# antenna.net
KiCad netlist of a schematic drawn in EAGLE
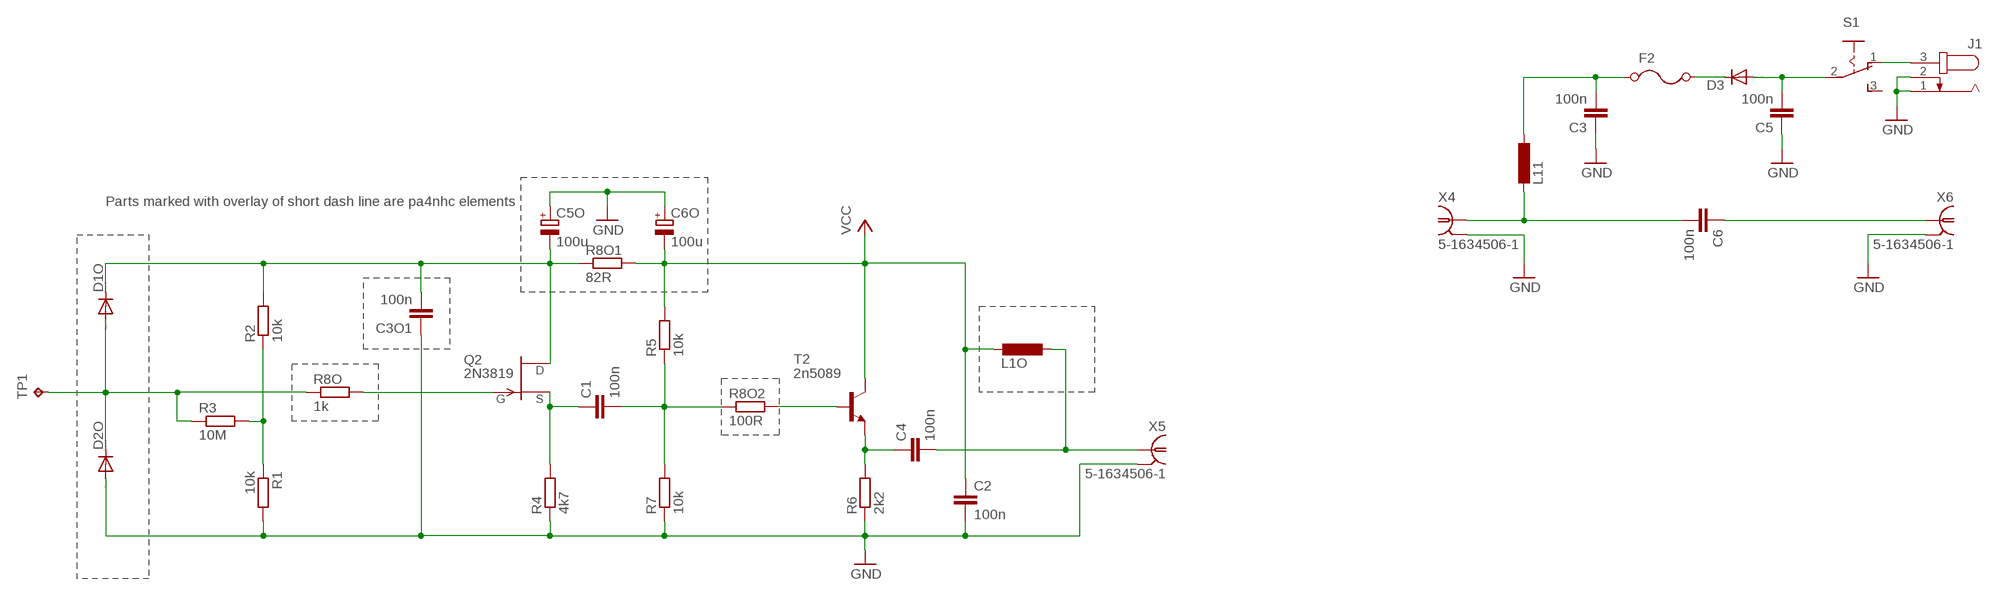
[diagram p0: schematic, sheet 1]

(export (version "E")
  (design (tool "Eeschema 10.0.6"))
  (components
    (comp (ref "C1")
      (value "100n")
      (footprint "eagle-import:C0805")
      (fields (field (name "MFR") "C0805C104K5RACTU"))
      (libsource (lib "eagle-import") (part "C-EUC0805"))
    )
    (comp (ref "C2")
      (value "100n")
      (footprint "eagle-import:C0805")
      (fields (field (name "MFR") "C0805C104K5RACTU"))
      (libsource (lib "eagle-import") (part "C-EUC0805"))
    )
    (comp (ref "C3")
      (value "100n")
      (footprint "eagle-import:C0805")
      (fields (field (name "MFR") "C0805C104K5RACTU"))
      (libsource (lib "eagle-import") (part "C-EUC0805"))
    )
    (comp (ref "C3O1")
      (value "100n")
      (footprint "eagle-import:C0805")
      (fields (field (name "MFR") "C0805C104K5RACTU"))
      (libsource (lib "eagle-import") (part "C-EUC0805"))
    )
    (comp (ref "C4")
      (value "100n")
      (footprint "eagle-import:C0805")
      (fields (field (name "MFR") "C0805C104K5RACTU"))
      (libsource (lib "eagle-import") (part "C-EUC0805"))
    )
    (comp (ref "C5")
      (value "100n")
      (footprint "eagle-import:C0805")
      (fields (field (name "MFR") "C0805C104K5RACTU"))
      (libsource (lib "eagle-import") (part "C-EUC0805"))
    )
    (comp (ref "C5O")
      (value "100u")
      (footprint "eagle-import:E2,5-7")
      (fields (field (name "MFR") "107CKS035M"))
      (libsource (lib "eagle-import") (part "CPOL-EUE2.5-7"))
    )
    (comp (ref "C6")
      (value "100n")
      (footprint "eagle-import:C0805")
      (fields (field (name "MFR") "C0805C104K5RACTU"))
      (libsource (lib "eagle-import") (part "C-EUC0805"))
    )
    (comp (ref "C6O")
      (value "100u")
      (footprint "eagle-import:E2,5-7")
      (fields (field (name "MFR") "107CKS035M"))
      (libsource (lib "eagle-import") (part "CPOL-EUE2.5-7"))
    )
    (comp (ref "D1O")
      (value "DIODE-DO214AC")
      (footprint "eagle-import:DO214AC")
      (fields (field (name "MFR") "FM4007W-W"))
      (libsource (lib "eagle-import") (part "DIODE-DO214AC"))
    )
    (comp (ref "D2O")
      (value "DIODE-DO214AC")
      (footprint "eagle-import:DO214AC")
      (fields (field (name "MFR") "FM4007W-W"))
      (libsource (lib "eagle-import") (part "DIODE-DO214AC"))
    )
    (comp (ref "D3")
      (value "DIODE-DO214AC")
      (footprint "eagle-import:DO214AC")
      (fields (field (name "MFR") "SSA33L-E3/5AT"))
      (libsource (lib "eagle-import") (part "DIODE-DO214AC"))
    )
    (comp (ref "F2")
      (value "0ZCG0150BF2C")
      (footprint "eagle-import:CN1812")
      (libsource (lib "eagle-import") (part "0ZCG0150BF2C"))
    )
    (comp (ref "J1")
      (value "JACK-PLUG0")
      (footprint "eagle-import:SPC4077")
      (fields (field (name "MFR") "FC68148 "))
      (libsource (lib "eagle-import") (part "JACK-PLUG0"))
    )
    (comp (ref "L1O")
      (value "L-EU0207/5V")
      (footprint "eagle-import:0207_5V")
      (fields (field (name "MFR") "RLB0914-101KL"))
      (libsource (lib "eagle-import") (part "L-EU0207/5V"))
    )
    (comp (ref "L11")
      (value "L-EU0207/5V")
      (footprint "eagle-import:0207_5V")
      (fields (field (name "MFR") "RLB0914-101KL"))
      (libsource (lib "eagle-import") (part "L-EU0207/5V"))
    )
    (comp (ref "Q2")
      (value "2N3819")
      (footprint "eagle-import:TO92")
      (fields (field (name "MFR") "2N3819 or 2N4859"))
      (libsource (lib "eagle-import") (part "2N3819"))
    )
    (comp (ref "R1")
      (value "10k")
      (footprint "eagle-import:M0805")
      (fields (field (name "MFR") "AS08J1002ET"))
      (libsource (lib "eagle-import") (part "R-EU_M0805"))
    )
    (comp (ref "R2")
      (value "10k")
      (footprint "eagle-import:M0805")
      (fields (field (name "MFR") "AS08J1002ET"))
      (libsource (lib "eagle-import") (part "R-EU_M0805"))
    )
    (comp (ref "R3")
      (value "10M")
      (footprint "eagle-import:M0805")
      (fields (field (name "MFR") "SG73S2ATTD106J"))
      (libsource (lib "eagle-import") (part "R-EU_M0805"))
    )
    (comp (ref "R4")
      (value "4k7")
      (footprint "eagle-import:M0805")
      (fields (field (name "MFR") "SG73S2ATTD472J"))
      (libsource (lib "eagle-import") (part "R-EU_M0805"))
    )
    (comp (ref "R5")
      (value "10k")
      (footprint "eagle-import:M0805")
      (fields (field (name "MFR") "AS08J1002ET"))
      (libsource (lib "eagle-import") (part "R-EU_M0805"))
    )
    (comp (ref "R6")
      (value "2k2")
      (footprint "eagle-import:R2010")
      (fields (field (name "MFR") "SG73P2ATTD222J"))
      (libsource (lib "eagle-import") (part "R-EU_R2010"))
    )
    (comp (ref "R7")
      (value "10k")
      (footprint "eagle-import:M0805")
      (fields (field (name "MFR") "AS08J1002ET"))
      (libsource (lib "eagle-import") (part "R-EU_M0805"))
    )
    (comp (ref "R8O")
      (value "1k")
      (footprint "eagle-import:M0805")
      (fields (field (name "MFR") "AS08J1001ET"))
      (libsource (lib "eagle-import") (part "R-EU_M0805"))
    )
    (comp (ref "R8O1")
      (value "82R")
      (footprint "eagle-import:M0805")
      (fields (field (name "MFR") "SG73S2ATTD820J"))
      (libsource (lib "eagle-import") (part "R-EU_M0805"))
    )
    (comp (ref "R8O2")
      (value "100R")
      (footprint "eagle-import:M1206")
      (fields (field (name "MFR") "AS08J1000ET"))
      (libsource (lib "eagle-import") (part "R-EU_M1206"))
    )
    (comp (ref "S1")
      (value "255SB")
      (footprint "eagle-import:255SB")
      (fields (field (name "MFR") "S1501 "))
      (libsource (lib "eagle-import") (part "255SB"))
    )
    (comp (ref "T2")
      (value "2n5089")
      (footprint "eagle-import:SOT23-EBC")
      (fields (field (name "MFR") "MMBT5089LT1G or 2N5109 or 2N3866"))
      (libsource (lib "eagle-import") (part "-NPN-SOT23-EBC"))
    )
    (comp (ref "TP1")
      (value "copper plate")
      (footprint "eagle-import:TP20SQ")
      (fields (field (name "MFR") "LHL08TB100K"))
      (libsource (lib "eagle-import") (part "TPTP20SQ"))
    )
    (comp (ref "X4")
      (value "5-1634506-1")
      (footprint "eagle-import:5-1634506-1")
      (libsource (lib "eagle-import") (part "5-1634506-1"))
    )
    (comp (ref "X5")
      (value "5-1634506-1")
      (footprint "eagle-import:5-1634506-1")
      (libsource (lib "eagle-import") (part "5-1634506-1"))
    )
    (comp (ref "X6")
      (value "5-1634506-1")
      (footprint "eagle-import:5-1634506-1")
      (libsource (lib "eagle-import") (part "5-1634506-1"))
    )
  )
  (nets
    (net (code "1") (name "GND") (class "Default")
      (node (ref "C2") (pin "2") (pinfunction "2_2") (pintype "passive"))
      (node (ref "C3") (pin "1") (pinfunction "1_1") (pintype "passive"))
      (node (ref "C3O1") (pin "1") (pinfunction "1_1") (pintype "passive"))
      (node (ref "C5") (pin "1") (pinfunction "1_1") (pintype "passive"))
      (node (ref "C5O") (pin "+") (pinfunction "+_+") (pintype "passive"))
      (node (ref "C6O") (pin "+") (pinfunction "+_+") (pintype "passive"))
      (node (ref "D2O") (pin "A") (pinfunction "A_A") (pintype "passive"))
      (node (ref "J1") (pin "1") (pinfunction "1_1") (pintype "passive"))
      (node (ref "J1") (pin "2") (pinfunction "2_2") (pintype "passive"))
      (node (ref "R1") (pin "2") (pinfunction "2_2") (pintype "passive"))
      (node (ref "R4") (pin "1") (pinfunction "1_1") (pintype "passive"))
      (node (ref "R6") (pin "1") (pinfunction "1_1") (pintype "passive"))
      (node (ref "R7") (pin "1") (pinfunction "1_1") (pintype "passive"))
      (node (ref "X4") (pin "2") (pinfunction "2_2") (pintype "passive"))
      (node (ref "X4") (pin "3") (pinfunction "2_3") (pintype "passive"))
      (node (ref "X4") (pin "4") (pinfunction "2_4") (pintype "passive"))
      (node (ref "X4") (pin "5") (pinfunction "2_5") (pintype "passive"))
      (node (ref "X5") (pin "2") (pinfunction "2_2") (pintype "passive"))
      (node (ref "X5") (pin "3") (pinfunction "2_3") (pintype "passive"))
      (node (ref "X5") (pin "4") (pinfunction "2_4") (pintype "passive"))
      (node (ref "X5") (pin "5") (pinfunction "2_5") (pintype "passive"))
      (node (ref "X6") (pin "2") (pinfunction "2_2") (pintype "passive"))
      (node (ref "X6") (pin "3") (pinfunction "2_3") (pintype "passive"))
      (node (ref "X6") (pin "4") (pinfunction "2_4") (pintype "passive"))
      (node (ref "X6") (pin "5") (pinfunction "2_5") (pintype "passive"))
    )
    (net (code "2") (name "Net-(C1-Pad2)") (class "Default")
      (node (ref "C1") (pin "2") (pinfunction "2_2") (pintype "passive"))
      (node (ref "R5") (pin "1") (pinfunction "1_1") (pintype "passive"))
      (node (ref "R7") (pin "2") (pinfunction "2_2") (pintype "passive"))
      (node (ref "R8O2") (pin "1") (pinfunction "1_1") (pintype "passive"))
    )
    (net (code "3") (name "Net-(C4-Pad1)") (class "Default")
      (node (ref "C4") (pin "1") (pinfunction "1_1") (pintype "passive"))
      (node (ref "R6") (pin "2") (pinfunction "2_2") (pintype "passive"))
      (node (ref "T2") (pin "E") (pinfunction "E_E") (pintype "passive"))
    )
    (net (code "4") (name "Net-(C4-Pad2)") (class "Default")
      (node (ref "C4") (pin "2") (pinfunction "2_2") (pintype "passive"))
      (node (ref "L1O") (pin "1") (pinfunction "1_1") (pintype "passive"))
      (node (ref "X5") (pin "1") (pinfunction "1_1") (pintype "passive"))
    )
    (net (code "5") (name "Net-(C6-Pad1)") (class "Default")
      (node (ref "C6") (pin "1") (pinfunction "1_1") (pintype "passive"))
      (node (ref "X6") (pin "1") (pinfunction "1_1") (pintype "passive"))
    )
    (net (code "6") (name "Net-(C6-Pad2)") (class "Default")
      (node (ref "C6") (pin "2") (pinfunction "2_2") (pintype "passive"))
      (node (ref "L11") (pin "2") (pinfunction "2_2") (pintype "passive"))
      (node (ref "X4") (pin "1") (pinfunction "1_1") (pintype "passive"))
    )
    (net (code "7") (name "Net-(D1O-PadA)") (class "Default")
      (node (ref "D1O") (pin "A") (pinfunction "A_A") (pintype "passive"))
      (node (ref "D2O") (pin "C") (pinfunction "C_C") (pintype "passive"))
      (node (ref "R3") (pin "1") (pinfunction "1_1") (pintype "passive"))
      (node (ref "R8O") (pin "1") (pinfunction "1_1") (pintype "passive"))
      (node (ref "TP1") (pin "TP") (pinfunction "TP_TP") (pintype "input"))
    )
    (net (code "8") (name "Net-(F2-1)") (class "Default")
      (node (ref "C3") (pin "2") (pinfunction "2_2") (pintype "passive"))
      (node (ref "F2") (pin "P$1") (pinfunction "1_P$1") (pintype "passive"))
      (node (ref "L11") (pin "1") (pinfunction "1_1") (pintype "passive"))
    )
    (net (code "9") (name "Net-(F2-2)") (class "Default")
      (node (ref "D3") (pin "C") (pinfunction "C_C") (pintype "passive"))
      (node (ref "F2") (pin "P$2") (pinfunction "2_P$2") (pintype "passive"))
    )
    (net (code "10") (name "Net-(Q2-D)") (class "Default")
      (node (ref "C3O1") (pin "2") (pinfunction "2_2") (pintype "passive"))
      (node (ref "C5O") (pin "-") (pinfunction "-_-") (pintype "passive"))
      (node (ref "D1O") (pin "C") (pinfunction "C_C") (pintype "passive"))
      (node (ref "Q2") (pin "1") (pinfunction "D_1") (pintype "passive"))
      (node (ref "R2") (pin "2") (pinfunction "2_2") (pintype "passive"))
      (node (ref "R8O1") (pin "1") (pinfunction "1_1") (pintype "passive"))
    )
    (net (code "11") (name "Net-(Q2-G)") (class "Default")
      (node (ref "Q2") (pin "2") (pinfunction "G_2") (pintype "passive"))
      (node (ref "R8O") (pin "2") (pinfunction "2_2") (pintype "passive"))
    )
    (net (code "12") (name "Net-(Q2-S)") (class "Default")
      (node (ref "C1") (pin "1") (pinfunction "1_1") (pintype "passive"))
      (node (ref "Q2") (pin "3") (pinfunction "S_3") (pintype "passive"))
      (node (ref "R4") (pin "2") (pinfunction "2_2") (pintype "passive"))
    )
    (net (code "13") (name "Net-(R1-Pad1)") (class "Default")
      (node (ref "R1") (pin "1") (pinfunction "1_1") (pintype "passive"))
      (node (ref "R2") (pin "1") (pinfunction "1_1") (pintype "passive"))
      (node (ref "R3") (pin "2") (pinfunction "2_2") (pintype "passive"))
    )
    (net (code "14") (name "Net-(R8O2-Pad2)") (class "Default")
      (node (ref "R8O2") (pin "2") (pinfunction "2_2") (pintype "passive"))
      (node (ref "T2") (pin "B") (pinfunction "B_B") (pintype "passive"))
    )
    (net (code "15") (name "Net-(S1-O)") (class "Default")
      (node (ref "J1") (pin "3") (pinfunction "3_3") (pintype "passive"))
      (node (ref "S1") (pin "1") (pinfunction "O_1") (pintype "passive"))
    )
    (net (code "16") (name "Net-(S1-P)") (class "Default")
      (node (ref "C5") (pin "2") (pinfunction "2_2") (pintype "passive"))
      (node (ref "D3") (pin "A") (pinfunction "A_A") (pintype "passive"))
      (node (ref "S1") (pin "2") (pinfunction "P_2") (pintype "passive"))
    )
    (net (code "17") (name "VCC") (class "Default")
      (node (ref "C2") (pin "1") (pinfunction "1_1") (pintype "passive"))
      (node (ref "C6O") (pin "-") (pinfunction "-_-") (pintype "passive"))
      (node (ref "L1O") (pin "2") (pinfunction "2_2") (pintype "passive"))
      (node (ref "R5") (pin "2") (pinfunction "2_2") (pintype "passive"))
      (node (ref "R8O1") (pin "2") (pinfunction "2_2") (pintype "passive"))
      (node (ref "T2") (pin "C") (pinfunction "C_C") (pintype "passive"))
    )
    (net (code "18") (name "unconnected-(S1-S-Pad3)") (class "Default")
      (node (ref "S1") (pin "3") (pinfunction "S_3") (pintype "passive"))
    )
  )
)
